# schematic.net
KiCad netlist of a schematic drawn in EasyEDA
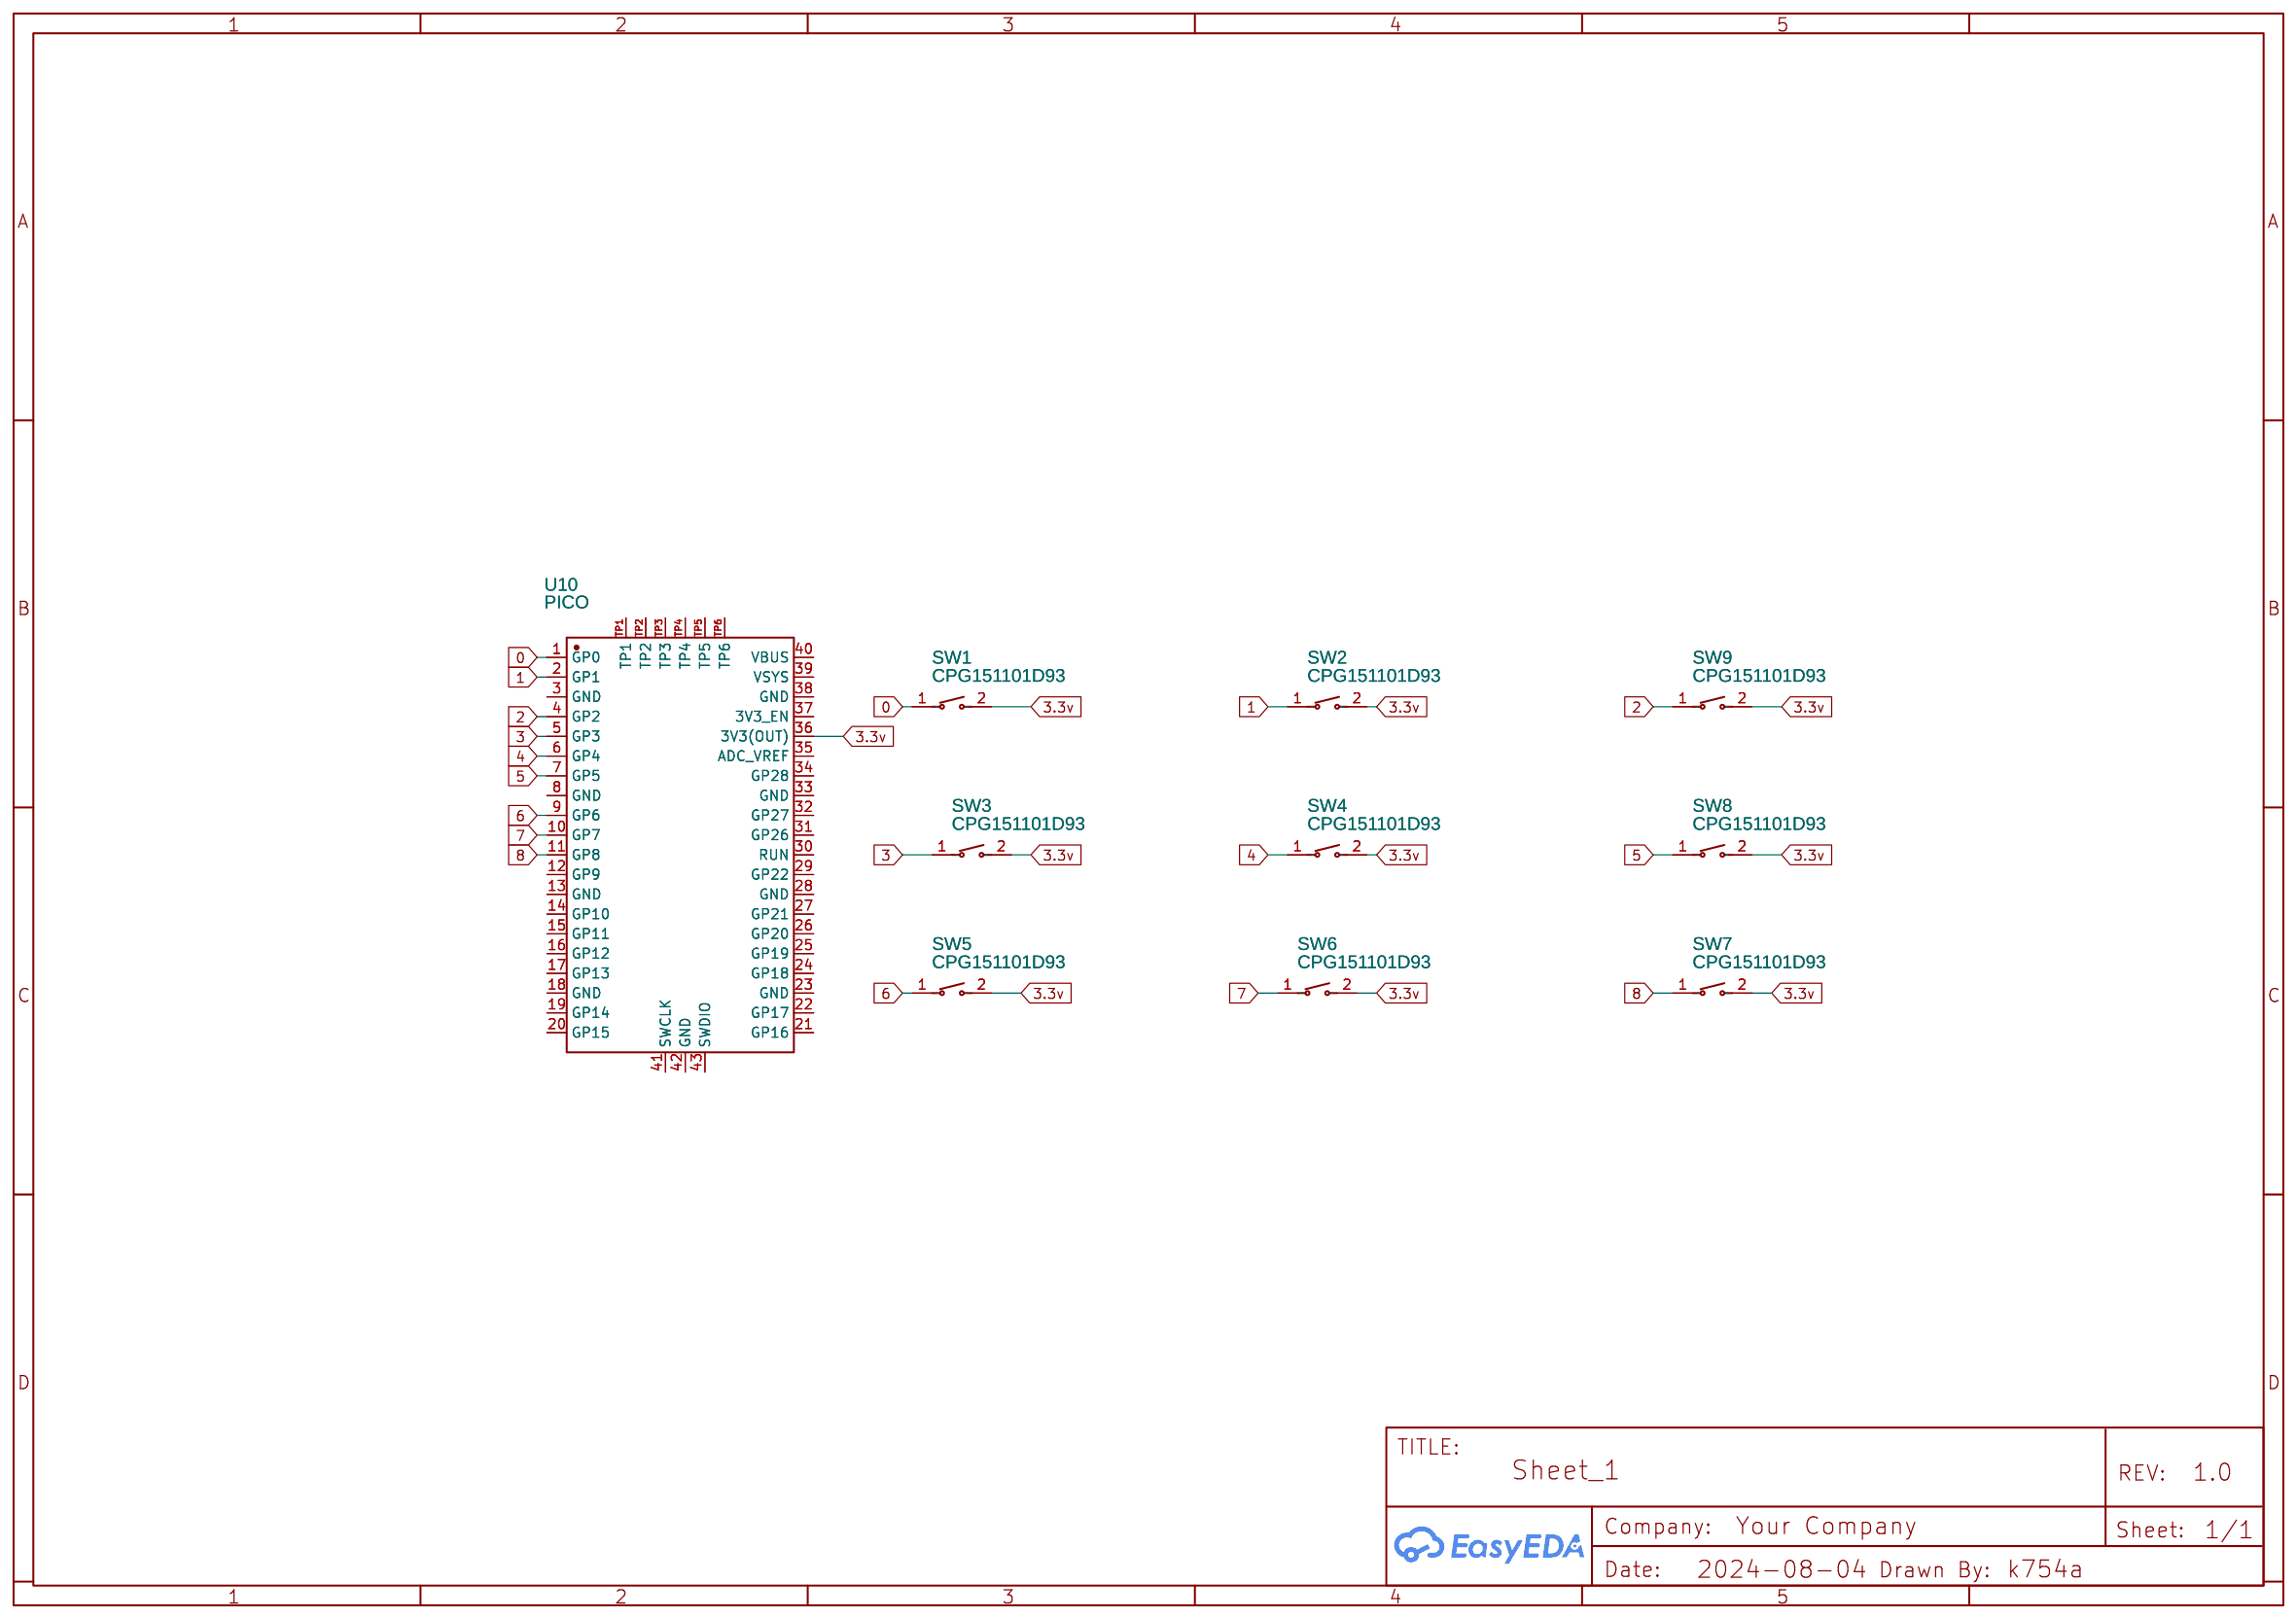
[diagram p0: schematic sheet]

(export (version "E")
  (design (tool "Eeschema 10.0.6"))
  (components
    (comp (ref "SW1")
      (value "CPG151101D93")
      (fields (field (name "Manufacturer") "Kailh(凯华)"))
      (libsource (lib "") (part "CPG151101D93"))
    )
    (comp (ref "SW2")
      (value "CPG151101D93")
      (fields (field (name "Manufacturer") "Kailh(凯华)"))
      (libsource (lib "") (part "CPG151101D93"))
    )
    (comp (ref "SW3")
      (value "CPG151101D93")
      (fields (field (name "Manufacturer") "Kailh(凯华)"))
      (libsource (lib "") (part "CPG151101D93"))
    )
    (comp (ref "SW4")
      (value "CPG151101D93")
      (fields (field (name "Manufacturer") "Kailh(凯华)"))
      (libsource (lib "") (part "CPG151101D93"))
    )
    (comp (ref "SW5")
      (value "CPG151101D93")
      (fields (field (name "Manufacturer") "Kailh(凯华)"))
      (libsource (lib "") (part "CPG151101D93"))
    )
    (comp (ref "SW6")
      (value "CPG151101D93")
      (fields (field (name "Manufacturer") "Kailh(凯华)"))
      (libsource (lib "") (part "CPG151101D93"))
    )
    (comp (ref "SW7")
      (value "CPG151101D93")
      (fields (field (name "Manufacturer") "Kailh(凯华)"))
      (libsource (lib "") (part "CPG151101D93"))
    )
    (comp (ref "SW8")
      (value "CPG151101D93")
      (fields (field (name "Manufacturer") "Kailh(凯华)"))
      (libsource (lib "") (part "CPG151101D93"))
    )
    (comp (ref "SW9")
      (value "CPG151101D93")
      (fields (field (name "Manufacturer") "Kailh(凯华)"))
      (libsource (lib "") (part "CPG151101D93"))
    )
    (comp (ref "U10")
      (value "PICO")
      (fields (field (name "Manufacturer") "Raspberry Pi(树莓派)"))
      (libsource (lib "") (part "PICO"))
    )
  )
  (nets
    (net (code "1") (name "0") (class "Default")
      (node (ref "SW1") (pin "1") (pinfunction "1_1") (pintype "unspecified"))
      (node (ref "U10") (pin "1") (pinfunction "GP0_1") (pintype "unspecified"))
    )
    (net (code "2") (name "1") (class "Default")
      (node (ref "SW2") (pin "1") (pinfunction "1_1") (pintype "unspecified"))
      (node (ref "U10") (pin "2") (pinfunction "GP1_2") (pintype "unspecified"))
    )
    (net (code "3") (name "2") (class "Default")
      (node (ref "SW9") (pin "1") (pinfunction "1_1") (pintype "unspecified"))
      (node (ref "U10") (pin "4") (pinfunction "GP2_4") (pintype "unspecified"))
    )
    (net (code "4") (name "3") (class "Default")
      (node (ref "SW3") (pin "1") (pinfunction "1_1") (pintype "unspecified"))
      (node (ref "U10") (pin "5") (pinfunction "GP3_5") (pintype "unspecified"))
    )
    (net (code "5") (name "3.3v") (class "Default")
      (node (ref "SW1") (pin "2") (pinfunction "2_2") (pintype "unspecified"))
      (node (ref "SW2") (pin "2") (pinfunction "2_2") (pintype "unspecified"))
      (node (ref "SW3") (pin "2") (pinfunction "2_2") (pintype "unspecified"))
      (node (ref "SW4") (pin "2") (pinfunction "2_2") (pintype "unspecified"))
      (node (ref "SW5") (pin "2") (pinfunction "2_2") (pintype "unspecified"))
      (node (ref "SW6") (pin "2") (pinfunction "2_2") (pintype "unspecified"))
      (node (ref "SW7") (pin "2") (pinfunction "2_2") (pintype "unspecified"))
      (node (ref "SW8") (pin "2") (pinfunction "2_2") (pintype "unspecified"))
      (node (ref "SW9") (pin "2") (pinfunction "2_2") (pintype "unspecified"))
      (node (ref "U10") (pin "36") (pinfunction "3V3(OUT)_36") (pintype "unspecified"))
    )
    (net (code "6") (name "4") (class "Default")
      (node (ref "SW4") (pin "1") (pinfunction "1_1") (pintype "unspecified"))
      (node (ref "U10") (pin "6") (pinfunction "GP4_6") (pintype "unspecified"))
    )
    (net (code "7") (name "5") (class "Default")
      (node (ref "SW8") (pin "1") (pinfunction "1_1") (pintype "unspecified"))
      (node (ref "U10") (pin "7") (pinfunction "GP5_7") (pintype "unspecified"))
    )
    (net (code "8") (name "6") (class "Default")
      (node (ref "SW5") (pin "1") (pinfunction "1_1") (pintype "unspecified"))
      (node (ref "U10") (pin "9") (pinfunction "GP6_9") (pintype "unspecified"))
    )
    (net (code "9") (name "7") (class "Default")
      (node (ref "SW6") (pin "1") (pinfunction "1_1") (pintype "unspecified"))
      (node (ref "U10") (pin "10") (pinfunction "GP7_10") (pintype "unspecified"))
    )
    (net (code "10") (name "8") (class "Default")
      (node (ref "SW7") (pin "1") (pinfunction "1_1") (pintype "unspecified"))
      (node (ref "U10") (pin "11") (pinfunction "GP8_11") (pintype "unspecified"))
    )
    (net (code "11") (name "unconnected-(U10-3V3_EN-Pad37)") (class "Default")
      (node (ref "U10") (pin "37") (pinfunction "3V3_EN_37") (pintype "unspecified"))
    )
    (net (code "12") (name "unconnected-(U10-ADC_VREF-Pad35)") (class "Default")
      (node (ref "U10") (pin "35") (pinfunction "ADC_VREF_35") (pintype "unspecified"))
    )
    (net (code "13") (name "unconnected-(U10-GND-Pad3)") (class "Default")
      (node (ref "U10") (pin "3") (pinfunction "GND_3") (pintype "unspecified"))
    )
    (net (code "14") (name "unconnected-(U10-GND-Pad8)") (class "Default")
      (node (ref "U10") (pin "8") (pinfunction "GND_8") (pintype "unspecified"))
    )
    (net (code "15") (name "unconnected-(U10-GND-Pad13)") (class "Default")
      (node (ref "U10") (pin "13") (pinfunction "GND_13") (pintype "unspecified"))
    )
    (net (code "16") (name "unconnected-(U10-GND-Pad18)") (class "Default")
      (node (ref "U10") (pin "18") (pinfunction "GND_18") (pintype "unspecified"))
    )
    (net (code "17") (name "unconnected-(U10-GND-Pad23)") (class "Default")
      (node (ref "U10") (pin "23") (pinfunction "GND_23") (pintype "unspecified"))
    )
    (net (code "18") (name "unconnected-(U10-GND-Pad28)") (class "Default")
      (node (ref "U10") (pin "28") (pinfunction "GND_28") (pintype "unspecified"))
    )
    (net (code "19") (name "unconnected-(U10-GND-Pad33)") (class "Default")
      (node (ref "U10") (pin "33") (pinfunction "GND_33") (pintype "unspecified"))
    )
    (net (code "20") (name "unconnected-(U10-GND-Pad38)") (class "Default")
      (node (ref "U10") (pin "38") (pinfunction "GND_38") (pintype "unspecified"))
    )
    (net (code "21") (name "unconnected-(U10-GND-Pad42)") (class "Default")
      (node (ref "U10") (pin "42") (pinfunction "GND_42") (pintype "unspecified"))
    )
    (net (code "22") (name "unconnected-(U10-GP9-Pad12)") (class "Default")
      (node (ref "U10") (pin "12") (pinfunction "GP9_12") (pintype "unspecified"))
    )
    (net (code "23") (name "unconnected-(U10-GP10-Pad14)") (class "Default")
      (node (ref "U10") (pin "14") (pinfunction "GP10_14") (pintype "unspecified"))
    )
    (net (code "24") (name "unconnected-(U10-GP11-Pad15)") (class "Default")
      (node (ref "U10") (pin "15") (pinfunction "GP11_15") (pintype "unspecified"))
    )
    (net (code "25") (name "unconnected-(U10-GP12-Pad16)") (class "Default")
      (node (ref "U10") (pin "16") (pinfunction "GP12_16") (pintype "unspecified"))
    )
    (net (code "26") (name "unconnected-(U10-GP13-Pad17)") (class "Default")
      (node (ref "U10") (pin "17") (pinfunction "GP13_17") (pintype "unspecified"))
    )
    (net (code "27") (name "unconnected-(U10-GP14-Pad19)") (class "Default")
      (node (ref "U10") (pin "19") (pinfunction "GP14_19") (pintype "unspecified"))
    )
    (net (code "28") (name "unconnected-(U10-GP15-Pad20)") (class "Default")
      (node (ref "U10") (pin "20") (pinfunction "GP15_20") (pintype "unspecified"))
    )
    (net (code "29") (name "unconnected-(U10-GP16-Pad21)") (class "Default")
      (node (ref "U10") (pin "21") (pinfunction "GP16_21") (pintype "unspecified"))
    )
    (net (code "30") (name "unconnected-(U10-GP17-Pad22)") (class "Default")
      (node (ref "U10") (pin "22") (pinfunction "GP17_22") (pintype "unspecified"))
    )
    (net (code "31") (name "unconnected-(U10-GP18-Pad24)") (class "Default")
      (node (ref "U10") (pin "24") (pinfunction "GP18_24") (pintype "unspecified"))
    )
    (net (code "32") (name "unconnected-(U10-GP19-Pad25)") (class "Default")
      (node (ref "U10") (pin "25") (pinfunction "GP19_25") (pintype "unspecified"))
    )
    (net (code "33") (name "unconnected-(U10-GP20-Pad26)") (class "Default")
      (node (ref "U10") (pin "26") (pinfunction "GP20_26") (pintype "unspecified"))
    )
    (net (code "34") (name "unconnected-(U10-GP21-Pad27)") (class "Default")
      (node (ref "U10") (pin "27") (pinfunction "GP21_27") (pintype "unspecified"))
    )
    (net (code "35") (name "unconnected-(U10-GP22-Pad29)") (class "Default")
      (node (ref "U10") (pin "29") (pinfunction "GP22_29") (pintype "unspecified"))
    )
    (net (code "36") (name "unconnected-(U10-GP26-Pad31)") (class "Default")
      (node (ref "U10") (pin "31") (pinfunction "GP26_31") (pintype "unspecified"))
    )
    (net (code "37") (name "unconnected-(U10-GP27-Pad32)") (class "Default")
      (node (ref "U10") (pin "32") (pinfunction "GP27_32") (pintype "unspecified"))
    )
    (net (code "38") (name "unconnected-(U10-GP28-Pad34)") (class "Default")
      (node (ref "U10") (pin "34") (pinfunction "GP28_34") (pintype "unspecified"))
    )
    (net (code "39") (name "unconnected-(U10-PadTP1)") (class "Default")
      (node (ref "U10") (pin "TP1") (pinfunction "TP1_TP1") (pintype "unspecified"))
    )
    (net (code "40") (name "unconnected-(U10-PadTP2)") (class "Default")
      (node (ref "U10") (pin "TP2") (pinfunction "TP2_TP2") (pintype "unspecified"))
    )
    (net (code "41") (name "unconnected-(U10-PadTP3)") (class "Default")
      (node (ref "U10") (pin "TP3") (pinfunction "TP3_TP3") (pintype "unspecified"))
    )
    (net (code "42") (name "unconnected-(U10-PadTP4)") (class "Default")
      (node (ref "U10") (pin "TP4") (pinfunction "TP4_TP4") (pintype "unspecified"))
    )
    (net (code "43") (name "unconnected-(U10-PadTP5)") (class "Default")
      (node (ref "U10") (pin "TP5") (pinfunction "TP5_TP5") (pintype "unspecified"))
    )
    (net (code "44") (name "unconnected-(U10-PadTP6)") (class "Default")
      (node (ref "U10") (pin "TP6") (pinfunction "TP6_TP6") (pintype "unspecified"))
    )
    (net (code "45") (name "unconnected-(U10-RUN-Pad30)") (class "Default")
      (node (ref "U10") (pin "30") (pinfunction "RUN_30") (pintype "unspecified"))
    )
    (net (code "46") (name "unconnected-(U10-SWCLK-Pad41)") (class "Default")
      (node (ref "U10") (pin "41") (pinfunction "SWCLK_41") (pintype "unspecified"))
    )
    (net (code "47") (name "unconnected-(U10-SWDIO-Pad43)") (class "Default")
      (node (ref "U10") (pin "43") (pinfunction "SWDIO_43") (pintype "unspecified"))
    )
    (net (code "48") (name "unconnected-(U10-VBUS-Pad40)") (class "Default")
      (node (ref "U10") (pin "40") (pinfunction "VBUS_40") (pintype "unspecified"))
    )
    (net (code "49") (name "unconnected-(U10-VSYS-Pad39)") (class "Default")
      (node (ref "U10") (pin "39") (pinfunction "VSYS_39") (pintype "unspecified"))
    )
  )
)
